# Utility_VCO.net
KiCad netlist of a schematic drawn in EAGLE
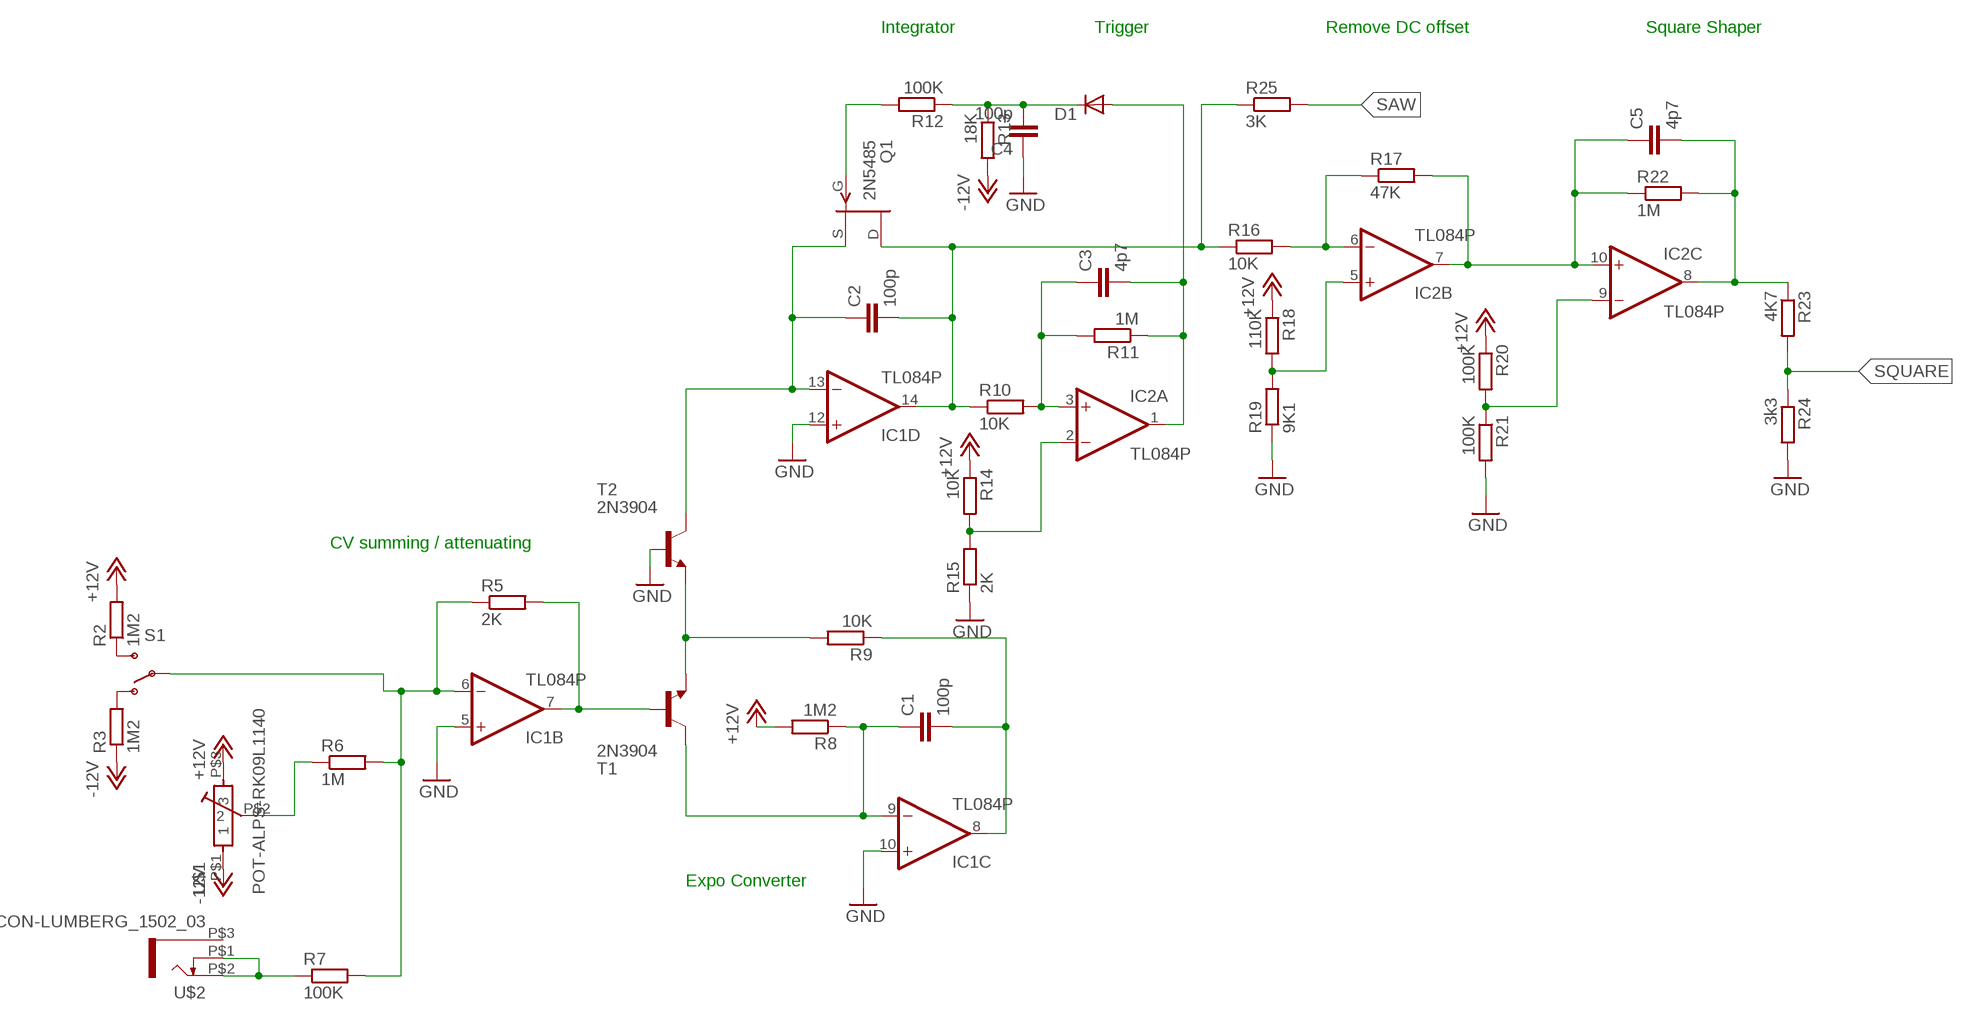
[diagram p0: schematic, sheet 1]

(export (version "E")
  (design (tool "Eeschema 10.0.6"))
  (components
    (comp (ref "C1")
      (value "100p")
      (footprint "eagle-import:C050-024X044")
      (libsource (lib "eagle-import") (part "C-EU050-024X044"))
    )
    (comp (ref "C2")
      (value "100p")
      (footprint "eagle-import:C050-024X044")
      (libsource (lib "eagle-import") (part "C-EU050-024X044"))
    )
    (comp (ref "C3")
      (value "4p7")
      (footprint "eagle-import:C050-024X044")
      (libsource (lib "eagle-import") (part "C-EU050-024X044"))
    )
    (comp (ref "C4")
      (value "100p")
      (footprint "eagle-import:C050-024X044")
      (libsource (lib "eagle-import") (part "C-EU050-024X044"))
    )
    (comp (ref "C5")
      (value "4p7")
      (footprint "eagle-import:C050-024X044")
      (libsource (lib "eagle-import") (part "C-EU050-024X044"))
    )
    (comp (ref "D1")
      (value "DIODE1N4148")
      (footprint "eagle-import:DIODE-1N4148")
      (libsource (lib "eagle-import") (part "DIODE1N4148"))
    )
    (comp (ref "IC1")
      (value "TL084P")
      (footprint "eagle-import:DIL14")
      (libsource (lib "eagle-import") (part "TL084P"))
    )
    (comp (ref "IC2")
      (value "TL084P")
      (footprint "eagle-import:DIL14")
      (libsource (lib "eagle-import") (part "TL084P"))
    )
    (comp (ref "Q1")
      (value "2N5485")
      (footprint "eagle-import:TO92-")
      (libsource (lib "eagle-import") (part "?5482N5"))
    )
    (comp (ref "R2")
      (value "1M2")
      (footprint "eagle-import:0204_7")
      (libsource (lib "eagle-import") (part "R-EU_0204/7"))
    )
    (comp (ref "R3")
      (value "1M2")
      (footprint "eagle-import:0204_7")
      (libsource (lib "eagle-import") (part "R-EU_0204/7"))
    )
    (comp (ref "R5")
      (value "2K")
      (footprint "eagle-import:0204_7")
      (libsource (lib "eagle-import") (part "R-EU_0204/7"))
    )
    (comp (ref "R6")
      (value "1M")
      (footprint "eagle-import:0204_7")
      (libsource (lib "eagle-import") (part "R-EU_0204/7"))
    )
    (comp (ref "R7")
      (value "100K")
      (footprint "eagle-import:0204_7")
      (libsource (lib "eagle-import") (part "R-EU_0204/7"))
    )
    (comp (ref "R8")
      (value "1M2")
      (footprint "eagle-import:0204_7")
      (libsource (lib "eagle-import") (part "R-EU_0204/7"))
    )
    (comp (ref "R9")
      (value "10K")
      (footprint "eagle-import:0204_7")
      (libsource (lib "eagle-import") (part "R-EU_0204/7"))
    )
    (comp (ref "R10")
      (value "10K")
      (footprint "eagle-import:0204_7")
      (libsource (lib "eagle-import") (part "R-EU_0204/7"))
    )
    (comp (ref "R11")
      (value "1M")
      (footprint "eagle-import:0204_7")
      (libsource (lib "eagle-import") (part "R-EU_0204/7"))
    )
    (comp (ref "R12")
      (value "100K")
      (footprint "eagle-import:0204_7")
      (libsource (lib "eagle-import") (part "R-EU_0204/7"))
    )
    (comp (ref "R13")
      (value "18K")
      (footprint "eagle-import:0204_7")
      (libsource (lib "eagle-import") (part "R-EU_0204/7"))
    )
    (comp (ref "R14")
      (value "10K")
      (footprint "eagle-import:0204_7")
      (libsource (lib "eagle-import") (part "R-EU_0204/7"))
    )
    (comp (ref "R15")
      (value "2K")
      (footprint "eagle-import:0204_7")
      (libsource (lib "eagle-import") (part "R-EU_0204/7"))
    )
    (comp (ref "R16")
      (value "10K")
      (footprint "eagle-import:0204_7")
      (libsource (lib "eagle-import") (part "R-EU_0204/7"))
    )
    (comp (ref "R17")
      (value "47K")
      (footprint "eagle-import:0204_7")
      (libsource (lib "eagle-import") (part "R-EU_0204/7"))
    )
    (comp (ref "R18")
      (value "110K")
      (footprint "eagle-import:0204_7")
      (libsource (lib "eagle-import") (part "R-EU_0204/7"))
    )
    (comp (ref "R19")
      (value "9K1")
      (footprint "eagle-import:0204_7")
      (libsource (lib "eagle-import") (part "R-EU_0204/7"))
    )
    (comp (ref "R20")
      (value "100K")
      (footprint "eagle-import:0204_7")
      (libsource (lib "eagle-import") (part "R-EU_0204/7"))
    )
    (comp (ref "R21")
      (value "100K")
      (footprint "eagle-import:0204_7")
      (libsource (lib "eagle-import") (part "R-EU_0204/7"))
    )
    (comp (ref "R22")
      (value "1M")
      (footprint "eagle-import:0204_7")
      (libsource (lib "eagle-import") (part "R-EU_0204/7"))
    )
    (comp (ref "R23")
      (value "4K7")
      (footprint "eagle-import:0204_7")
      (libsource (lib "eagle-import") (part "R-EU_0204/7"))
    )
    (comp (ref "R24")
      (value "3k3")
      (footprint "eagle-import:0204_7")
      (libsource (lib "eagle-import") (part "R-EU_0204/7"))
    )
    (comp (ref "R25")
      (value "3K")
      (footprint "eagle-import:0204_7")
      (libsource (lib "eagle-import") (part "R-EU_0204/7"))
    )
    (comp (ref "S1")
      (value "SWITCH-SPST")
      (footprint "eagle-import:SWITCH-SPDT-SALECOM-T8014")
      (libsource (lib "eagle-import") (part "SWITCH-SPST"))
    )
    (comp (ref "T1")
      (value "2N3904")
      (footprint "eagle-import:TO92")
      (libsource (lib "eagle-import") (part "2N3904"))
    )
    (comp (ref "T2")
      (value "2N3904")
      (footprint "eagle-import:TO92")
      (libsource (lib "eagle-import") (part "2N3904"))
    )
    (comp (ref "U$1")
      (value "POT-ALPS-RK09L1140")
      (footprint "eagle-import:POT-ALPS-RK09L1140")
      (libsource (lib "eagle-import") (part "POT-ALPS-RK09L1140"))
    )
    (comp (ref "U$2")
      (value "CON-LUMBERG_1502_03")
      (footprint "eagle-import:CON-LUMBERG_1502_03")
      (libsource (lib "eagle-import") (part "CON-LUMBERG_1502_03"))
    )
  )
  (nets
    (net (code "1") (name "+12V") (class "Default")
      (node (ref "R14") (pin "1") (pinfunction "1_1") (pintype "passive"))
      (node (ref "R18") (pin "1") (pinfunction "1_1") (pintype "passive"))
      (node (ref "R2") (pin "2") (pinfunction "2_2") (pintype "passive"))
      (node (ref "R20") (pin "1") (pinfunction "1_1") (pintype "passive"))
      (node (ref "R8") (pin "2") (pinfunction "2_2") (pintype "passive"))
      (node (ref "U$1") (pin "P$3") (pinfunction "3_P$3") (pintype "bidirectional"))
    )
    (net (code "2") (name "-12V") (class "Default")
      (node (ref "R13") (pin "2") (pinfunction "2_2") (pintype "passive"))
      (node (ref "R3") (pin "1") (pinfunction "1_1") (pintype "passive"))
      (node (ref "U$1") (pin "P$1") (pinfunction "1_P$1") (pintype "bidirectional"))
    )
    (net (code "3") (name "GND") (class "Default")
      (node (ref "C4") (pin "1") (pinfunction "1_1") (pintype "passive"))
      (node (ref "IC1") (pin "10") (pinfunction "+IN_10") (pintype "input"))
      (node (ref "IC1") (pin "12") (pinfunction "+IN_12") (pintype "input"))
      (node (ref "IC1") (pin "5") (pinfunction "+IN_5") (pintype "input"))
      (node (ref "R15") (pin "1") (pinfunction "1_1") (pintype "passive"))
      (node (ref "R19") (pin "1") (pinfunction "1_1") (pintype "passive"))
      (node (ref "R21") (pin "2") (pinfunction "2_2") (pintype "passive"))
      (node (ref "R24") (pin "2") (pinfunction "2_2") (pintype "passive"))
      (node (ref "T2") (pin "2") (pinfunction "B_2") (pintype "passive"))
    )
    (net (code "4") (name "Net-(C4-Pad2)") (class "Default")
      (node (ref "C4") (pin "2") (pinfunction "2_2") (pintype "passive"))
      (node (ref "D1") (pin "C") (pinfunction "C_C") (pintype "passive"))
      (node (ref "R12") (pin "1") (pinfunction "1_1") (pintype "passive"))
      (node (ref "R13") (pin "1") (pinfunction "1_1") (pintype "passive"))
    )
    (net (code "5") (name "Net-(IC1B--IN)") (class "Default")
      (node (ref "IC1") (pin "6") (pinfunction "-IN_6") (pintype "input"))
      (node (ref "R5") (pin "1") (pinfunction "1_1") (pintype "passive"))
      (node (ref "R6") (pin "2") (pinfunction "2_2") (pintype "passive"))
      (node (ref "R7") (pin "2") (pinfunction "2_2") (pintype "passive"))
      (node (ref "S1") (pin "2") (pinfunction "P_2") (pintype "passive"))
    )
    (net (code "6") (name "Net-(IC1B-OUT)") (class "Default")
      (node (ref "IC1") (pin "7") (pinfunction "OUT_7") (pintype "output"))
      (node (ref "R5") (pin "2") (pinfunction "2_2") (pintype "passive"))
      (node (ref "T1") (pin "2") (pinfunction "B_2") (pintype "passive"))
    )
    (net (code "7") (name "Net-(IC1C--IN)") (class "Default")
      (node (ref "C1") (pin "1") (pinfunction "1_1") (pintype "passive"))
      (node (ref "IC1") (pin "9") (pinfunction "-IN_9") (pintype "input"))
      (node (ref "R8") (pin "1") (pinfunction "1_1") (pintype "passive"))
      (node (ref "T1") (pin "1") (pinfunction "C_1") (pintype "passive"))
    )
    (net (code "8") (name "Net-(IC1C-OUT)") (class "Default")
      (node (ref "C1") (pin "2") (pinfunction "2_2") (pintype "passive"))
      (node (ref "IC1") (pin "8") (pinfunction "OUT_8") (pintype "output"))
      (node (ref "R9") (pin "1") (pinfunction "1_1") (pintype "passive"))
    )
    (net (code "9") (name "Net-(IC1D--IN)") (class "Default")
      (node (ref "C2") (pin "1") (pinfunction "1_1") (pintype "passive"))
      (node (ref "IC1") (pin "13") (pinfunction "-IN_13") (pintype "input"))
      (node (ref "Q1") (pin "2") (pinfunction "S_2") (pintype "passive"))
      (node (ref "T2") (pin "1") (pinfunction "C_1") (pintype "passive"))
    )
    (net (code "10") (name "Net-(IC1D-OUT)") (class "Default")
      (node (ref "C2") (pin "2") (pinfunction "2_2") (pintype "passive"))
      (node (ref "IC1") (pin "14") (pinfunction "OUT_14") (pintype "output"))
      (node (ref "Q1") (pin "3") (pinfunction "D_3") (pintype "passive"))
      (node (ref "R10") (pin "1") (pinfunction "1_1") (pintype "passive"))
      (node (ref "R16") (pin "1") (pinfunction "1_1") (pintype "passive"))
      (node (ref "R25") (pin "1") (pinfunction "1_1") (pintype "passive"))
    )
    (net (code "11") (name "Net-(IC2A-+IN)") (class "Default")
      (node (ref "C3") (pin "1") (pinfunction "1_1") (pintype "passive"))
      (node (ref "IC2") (pin "3") (pinfunction "+IN_3") (pintype "input"))
      (node (ref "R10") (pin "2") (pinfunction "2_2") (pintype "passive"))
      (node (ref "R11") (pin "2") (pinfunction "2_2") (pintype "passive"))
    )
    (net (code "12") (name "Net-(IC2A--IN)") (class "Default")
      (node (ref "IC2") (pin "2") (pinfunction "-IN_2") (pintype "input"))
      (node (ref "R14") (pin "2") (pinfunction "2_2") (pintype "passive"))
      (node (ref "R15") (pin "2") (pinfunction "2_2") (pintype "passive"))
    )
    (net (code "13") (name "Net-(IC2A-OUT)") (class "Default")
      (node (ref "C3") (pin "2") (pinfunction "2_2") (pintype "passive"))
      (node (ref "D1") (pin "A") (pinfunction "A_A") (pintype "passive"))
      (node (ref "IC2") (pin "1") (pinfunction "OUT_1") (pintype "output"))
      (node (ref "R11") (pin "1") (pinfunction "1_1") (pintype "passive"))
    )
    (net (code "14") (name "Net-(IC2B-+IN)") (class "Default")
      (node (ref "IC2") (pin "5") (pinfunction "+IN_5") (pintype "input"))
      (node (ref "R18") (pin "2") (pinfunction "2_2") (pintype "passive"))
      (node (ref "R19") (pin "2") (pinfunction "2_2") (pintype "passive"))
    )
    (net (code "15") (name "Net-(IC2B--IN)") (class "Default")
      (node (ref "IC2") (pin "6") (pinfunction "-IN_6") (pintype "input"))
      (node (ref "R16") (pin "2") (pinfunction "2_2") (pintype "passive"))
      (node (ref "R17") (pin "1") (pinfunction "1_1") (pintype "passive"))
    )
    (net (code "16") (name "Net-(IC2B-OUT)") (class "Default")
      (node (ref "C5") (pin "1") (pinfunction "1_1") (pintype "passive"))
      (node (ref "IC2") (pin "10") (pinfunction "+IN_10") (pintype "input"))
      (node (ref "IC2") (pin "7") (pinfunction "OUT_7") (pintype "output"))
      (node (ref "R17") (pin "2") (pinfunction "2_2") (pintype "passive"))
      (node (ref "R22") (pin "1") (pinfunction "1_1") (pintype "passive"))
    )
    (net (code "17") (name "Net-(IC2C--IN)") (class "Default")
      (node (ref "IC2") (pin "9") (pinfunction "-IN_9") (pintype "input"))
      (node (ref "R20") (pin "2") (pinfunction "2_2") (pintype "passive"))
      (node (ref "R21") (pin "1") (pinfunction "1_1") (pintype "passive"))
    )
    (net (code "18") (name "Net-(IC2C-OUT)") (class "Default")
      (node (ref "C5") (pin "2") (pinfunction "2_2") (pintype "passive"))
      (node (ref "IC2") (pin "8") (pinfunction "OUT_8") (pintype "output"))
      (node (ref "R22") (pin "2") (pinfunction "2_2") (pintype "passive"))
      (node (ref "R23") (pin "1") (pinfunction "1_1") (pintype "passive"))
    )
    (net (code "19") (name "Net-(Q1-G)") (class "Default")
      (node (ref "Q1") (pin "1") (pinfunction "G_1") (pintype "passive"))
      (node (ref "R12") (pin "2") (pinfunction "2_2") (pintype "passive"))
    )
    (net (code "20") (name "Net-(S1-O)") (class "Default")
      (node (ref "R3") (pin "2") (pinfunction "2_2") (pintype "passive"))
      (node (ref "S1") (pin "1") (pinfunction "O_1") (pintype "passive"))
    )
    (net (code "21") (name "Net-(S1-S)") (class "Default")
      (node (ref "R2") (pin "1") (pinfunction "1_1") (pintype "passive"))
      (node (ref "S1") (pin "3") (pinfunction "S_3") (pintype "passive"))
    )
    (net (code "22") (name "Net-(T1-E)") (class "Default")
      (node (ref "R9") (pin "2") (pinfunction "2_2") (pintype "passive"))
      (node (ref "T1") (pin "3") (pinfunction "E_3") (pintype "passive"))
      (node (ref "T2") (pin "3") (pinfunction "E_3") (pintype "passive"))
    )
    (net (code "23") (name "Net-(U$1A-2)") (class "Default")
      (node (ref "R6") (pin "1") (pinfunction "1_1") (pintype "passive"))
      (node (ref "U$1") (pin "P$2") (pinfunction "2_P$2") (pintype "bidirectional"))
    )
    (net (code "24") (name "Net-(U$2-3)") (class "Default")
      (node (ref "R7") (pin "1") (pinfunction "1_1") (pintype "passive"))
      (node (ref "U$2") (pin "P$1") (pinfunction "4_P$1") (pintype "passive"))
      (node (ref "U$2") (pin "P$2") (pinfunction "3_P$2") (pintype "passive"))
    )
    (net (code "25") (name "SAW") (class "Default")
      (node (ref "R25") (pin "2") (pinfunction "2_2") (pintype "passive"))
    )
    (net (code "26") (name "SQUARE") (class "Default")
      (node (ref "R23") (pin "2") (pinfunction "2_2") (pintype "passive"))
      (node (ref "R24") (pin "1") (pinfunction "1_1") (pintype "passive"))
    )
    (net (code "27") (name "unconnected-(U$2-5-PadP$3)") (class "Default")
      (node (ref "U$2") (pin "P$3") (pinfunction "5_P$3") (pintype "passive"))
    )
  )
)
